# STRWHL-S08-V00-ButtonInput.net
KiCad netlist of a schematic drawn in Altium Designer
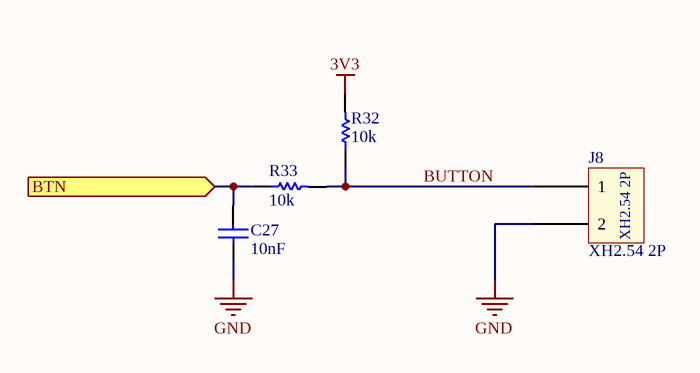
[diagram p0: STRWHL-S08-V00-ButtonInput.SchDoc]

(export (version "E")
  (design (tool "Eeschema 10.0.6"))
  (components
    (comp (ref "C27")
      (value "10nF")
      (footprint "Cap_Ceramic_0603")
      (description "Capacitor, Ceramic, SMD, 10nF, 50V, 5%, X7R, 0603")
      (libsource (lib "StandardCapacitors") (part "10nF 50V 5% X7R 0603"))
    )
    (comp (ref "J8")
      (value "XH2.54 2P")
      (footprint "JST_XH254_2P_TH_RH")
      (libsource (lib "JST_XH254") (part "XH2.54 2P"))
    )
    (comp (ref "R32")
      (value "10k")
      (footprint "Res_ThinFilm_0603")
      (description "Resistor, SMD, 10k, 0.1W, 5%, 0603")
      (libsource (lib "StandardResistors") (part "10k 5% 0603"))
    )
    (comp (ref "R33")
      (value "10k")
      (footprint "Res_ThinFilm_0603")
      (description "Resistor, SMD, 10k, 0.1W, 5%, 0603")
      (libsource (lib "StandardResistors") (part "10k 5% 0603"))
    )
  )
  (nets
    (net (code "1") (name "/BTN") (class "Default")
      (node (ref "C27") (pin "2") (pinfunction "2_2") (pintype "passive"))
      (node (ref "R33") (pin "1") (pinfunction "1_1") (pintype "passive"))
    )
    (net (code "2") (name "/BUTTON") (class "Default")
      (node (ref "J8") (pin "1") (pinfunction "1_1") (pintype "passive"))
      (node (ref "R32") (pin "1") (pinfunction "1_1") (pintype "passive"))
      (node (ref "R33") (pin "2") (pinfunction "2_2") (pintype "passive"))
    )
    (net (code "3") (name "3V3") (class "Default")
      (node (ref "R32") (pin "2") (pinfunction "2_2") (pintype "passive"))
    )
    (net (code "4") (name "GND") (class "Default")
      (node (ref "C27") (pin "1") (pinfunction "1_1") (pintype "passive"))
      (node (ref "J8") (pin "2") (pinfunction "2_2") (pintype "passive"))
    )
  )
)
